# fonte_simetrica.net
KiCad netlist of a schematic drawn in EAGLE
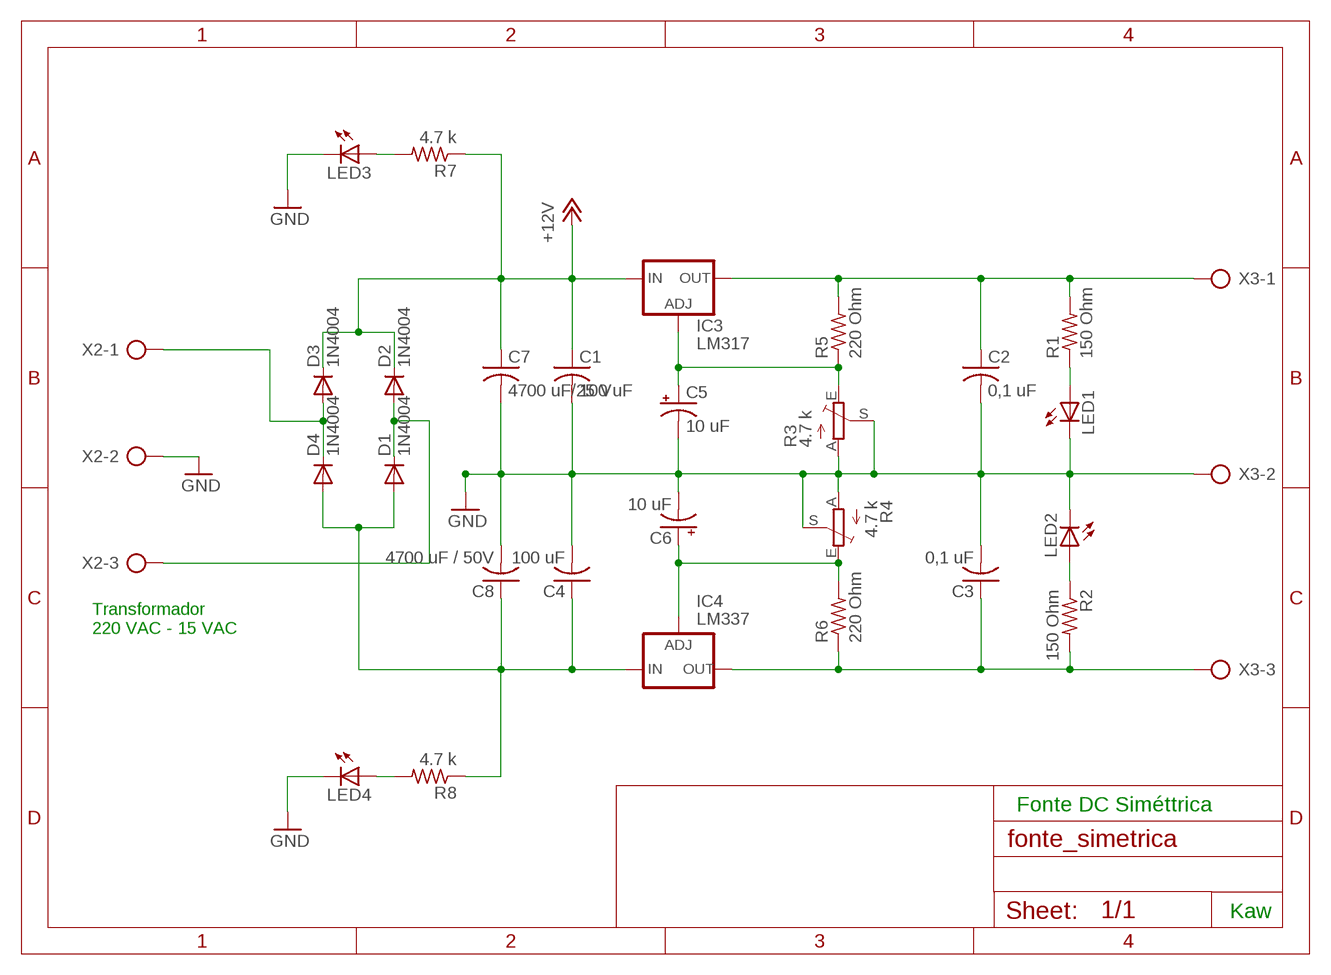
[diagram p0: schematic, sheet 1]

(export (version "E")
  (design (tool "Eeschema 10.0.6"))
  (components
    (comp (ref "C1")
      (value "100 uF")
      (footprint "eagle-import:C025-025X050")
      (libsource (lib "eagle-import") (part "C-US025-025X050"))
    )
    (comp (ref "C2")
      (value "0,1 uF")
      (footprint "eagle-import:C025-025X050")
      (libsource (lib "eagle-import") (part "C-US025-025X050"))
    )
    (comp (ref "C3")
      (value "0,1 uF")
      (footprint "eagle-import:C025-025X050")
      (libsource (lib "eagle-import") (part "C-US025-025X050"))
    )
    (comp (ref "C4")
      (value "100 uF")
      (footprint "eagle-import:C025-025X050")
      (libsource (lib "eagle-import") (part "C-US025-025X050"))
    )
    (comp (ref "C5")
      (value "10 uF")
      (footprint "eagle-import:E2,5-4R")
      (libsource (lib "eagle-import") (part "CPOL-USE2.5-5V"))
    )
    (comp (ref "C6")
      (value "10 uF")
      (footprint "eagle-import:E2,5-4R")
      (libsource (lib "eagle-import") (part "CPOL-USE2.5-5V"))
    )
    (comp (ref "C7")
      (value "4700 uF/25 V")
      (footprint "eagle-import:C025-025X050")
      (libsource (lib "eagle-import") (part "C-US025-025X050"))
    )
    (comp (ref "C8")
      (value "4700 uF / 50V")
      (footprint "eagle-import:C025-025X050")
      (libsource (lib "eagle-import") (part "C-US025-025X050"))
    )
    (comp (ref "D1")
      (value "1N4004")
      (footprint "eagle-import:DO41-10")
      (libsource (lib "eagle-import") (part "1N4004"))
    )
    (comp (ref "D2")
      (value "1N4004")
      (footprint "eagle-import:DO41-10")
      (libsource (lib "eagle-import") (part "1N4004"))
    )
    (comp (ref "D3")
      (value "1N4004")
      (footprint "eagle-import:DO41-10")
      (libsource (lib "eagle-import") (part "1N4004"))
    )
    (comp (ref "D4")
      (value "1N4004")
      (footprint "eagle-import:DO41-10")
      (libsource (lib "eagle-import") (part "1N4004"))
    )
    (comp (ref "IC3")
      (value "LM317")
      (footprint "eagle-import:317TS")
      (libsource (lib "eagle-import") (part "LM317TS"))
    )
    (comp (ref "IC4")
      (value "LM337")
      (footprint "eagle-import:337TS")
      (libsource (lib "eagle-import") (part "LM337TS"))
    )
    (comp (ref "LED1")
      (value "LED5MM")
      (footprint "eagle-import:LED5MM")
      (libsource (lib "eagle-import") (part "LED5MM"))
    )
    (comp (ref "LED2")
      (value "LED5MM")
      (footprint "eagle-import:LED5MM")
      (libsource (lib "eagle-import") (part "LED5MM"))
    )
    (comp (ref "LED3")
      (value "LED5MM")
      (footprint "eagle-import:LED5MM")
      (libsource (lib "eagle-import") (part "LED5MM"))
    )
    (comp (ref "LED4")
      (value "LED5MM")
      (footprint "eagle-import:LED5MM")
      (libsource (lib "eagle-import") (part "LED5MM"))
    )
    (comp (ref "R1")
      (value "150 Ohm")
      (footprint "eagle-import:0207_5V")
      (libsource (lib "eagle-import") (part "R-US_0207/5V"))
    )
    (comp (ref "R2")
      (value "150 Ohm")
      (footprint "eagle-import:0207_5V")
      (libsource (lib "eagle-import") (part "R-US_0207/5V"))
    )
    (comp (ref "R3")
      (value "4.7 k")
      (footprint "eagle-import:S64W")
      (libsource (lib "eagle-import") (part "TRIM_EU-S64W"))
    )
    (comp (ref "R4")
      (value "4.7 k")
      (footprint "eagle-import:S64W")
      (libsource (lib "eagle-import") (part "TRIM_EU-S64W"))
    )
    (comp (ref "R5")
      (value "220 Ohm")
      (footprint "eagle-import:0207_5V")
      (libsource (lib "eagle-import") (part "R-US_0207/5V"))
    )
    (comp (ref "R6")
      (value "220 Ohm")
      (footprint "eagle-import:0207_5V")
      (libsource (lib "eagle-import") (part "R-US_0207/5V"))
    )
    (comp (ref "R7")
      (value "4.7 k")
      (footprint "eagle-import:0207_5V")
      (libsource (lib "eagle-import") (part "R-US_0207/5V"))
    )
    (comp (ref "R8")
      (value "4.7 k")
      (footprint "eagle-import:0207_5V")
      (libsource (lib "eagle-import") (part "R-US_0207/5V"))
    )
    (comp (ref "X2")
      (value "AK300/3")
      (footprint "eagle-import:AK300_3")
      (libsource (lib "eagle-import") (part "AK300/3"))
    )
    (comp (ref "X3")
      (value "AK300/3")
      (footprint "eagle-import:AK300_3")
      (libsource (lib "eagle-import") (part "AK300/3"))
    )
  )
  (nets
    (net (code "1") (name "+12V") (class "Default")
      (node (ref "C1") (pin "1") (pinfunction "1_1") (pintype "passive"))
      (node (ref "C7") (pin "1") (pinfunction "1_1") (pintype "passive"))
      (node (ref "D2") (pin "C") (pinfunction "C_C") (pintype "passive"))
      (node (ref "D3") (pin "C") (pinfunction "C_C") (pintype "passive"))
      (node (ref "IC3") (pin "3") (pinfunction "IN_3") (pintype "input"))
      (node (ref "R7") (pin "1") (pinfunction "1_1") (pintype "passive"))
    )
    (net (code "2") (name "GND") (class "Default")
      (node (ref "C1") (pin "2") (pinfunction "2_2") (pintype "passive"))
      (node (ref "C2") (pin "2") (pinfunction "2_2") (pintype "passive"))
      (node (ref "C3") (pin "2") (pinfunction "2_2") (pintype "passive"))
      (node (ref "C4") (pin "2") (pinfunction "2_2") (pintype "passive"))
      (node (ref "C5") (pin "-") (pinfunction "-_-") (pintype "passive"))
      (node (ref "C6") (pin "-") (pinfunction "-_-") (pintype "passive"))
      (node (ref "C7") (pin "2") (pinfunction "2_2") (pintype "passive"))
      (node (ref "C8") (pin "2") (pinfunction "2_2") (pintype "passive"))
      (node (ref "LED1") (pin "K") (pinfunction "C_K") (pintype "passive"))
      (node (ref "LED2") (pin "K") (pinfunction "C_K") (pintype "passive"))
      (node (ref "LED3") (pin "K") (pinfunction "C_K") (pintype "passive"))
      (node (ref "LED4") (pin "K") (pinfunction "C_K") (pintype "passive"))
      (node (ref "R3") (pin "A") (pinfunction "A_A") (pintype "passive"))
      (node (ref "R3") (pin "S") (pinfunction "S_S") (pintype "passive"))
      (node (ref "R4") (pin "A") (pinfunction "A_A") (pintype "passive"))
      (node (ref "R4") (pin "S") (pinfunction "S_S") (pintype "passive"))
      (node (ref "X2") (pin "2") (pinfunction "KL_2") (pintype "passive"))
      (node (ref "X3") (pin "2") (pinfunction "KL_2") (pintype "passive"))
    )
    (net (code "3") (name "Net-(IC3-ADJ)") (class "Default")
      (node (ref "C5") (pin "+") (pinfunction "+_+") (pintype "passive"))
      (node (ref "IC3") (pin "1") (pinfunction "ADJ_1") (pintype "input"))
      (node (ref "R3") (pin "E") (pinfunction "E_E") (pintype "passive"))
      (node (ref "R5") (pin "1") (pinfunction "1_1") (pintype "passive"))
    )
    (net (code "4") (name "Net-(IC3-OUT)") (class "Default")
      (node (ref "C2") (pin "1") (pinfunction "1_1") (pintype "passive"))
      (node (ref "IC3") (pin "2") (pinfunction "OUT_2") (pintype "passive"))
      (node (ref "R1") (pin "2") (pinfunction "2_2") (pintype "passive"))
      (node (ref "R5") (pin "2") (pinfunction "2_2") (pintype "passive"))
      (node (ref "X3") (pin "1") (pinfunction "KL_1") (pintype "passive"))
    )
    (net (code "5") (name "Net-(IC4-ADJ)") (class "Default")
      (node (ref "C6") (pin "+") (pinfunction "+_+") (pintype "passive"))
      (node (ref "IC4") (pin "1") (pinfunction "ADJ_1") (pintype "input"))
      (node (ref "R4") (pin "E") (pinfunction "E_E") (pintype "passive"))
      (node (ref "R6") (pin "2") (pinfunction "2_2") (pintype "passive"))
    )
    (net (code "6") (name "Net-(IC4-IN)") (class "Default")
      (node (ref "C4") (pin "1") (pinfunction "1_1") (pintype "passive"))
      (node (ref "C8") (pin "1") (pinfunction "1_1") (pintype "passive"))
      (node (ref "D1") (pin "A") (pinfunction "A_A") (pintype "passive"))
      (node (ref "D4") (pin "A") (pinfunction "A_A") (pintype "passive"))
      (node (ref "IC4") (pin "2") (pinfunction "IN_2") (pintype "input"))
      (node (ref "R8") (pin "1") (pinfunction "1_1") (pintype "passive"))
    )
    (net (code "7") (name "Net-(IC4-OUT)") (class "Default")
      (node (ref "C3") (pin "1") (pinfunction "1_1") (pintype "passive"))
      (node (ref "IC4") (pin "3") (pinfunction "OUT_3") (pintype "passive"))
      (node (ref "R2") (pin "2") (pinfunction "2_2") (pintype "passive"))
      (node (ref "R6") (pin "1") (pinfunction "1_1") (pintype "passive"))
      (node (ref "X3") (pin "3") (pinfunction "KL_3") (pintype "passive"))
    )
    (net (code "8") (name "Net-(LED1-PadA)") (class "Default")
      (node (ref "LED1") (pin "A") (pinfunction "A_A") (pintype "passive"))
      (node (ref "R1") (pin "1") (pinfunction "1_1") (pintype "passive"))
    )
    (net (code "9") (name "Net-(LED2-PadA)") (class "Default")
      (node (ref "LED2") (pin "A") (pinfunction "A_A") (pintype "passive"))
      (node (ref "R2") (pin "1") (pinfunction "1_1") (pintype "passive"))
    )
    (net (code "10") (name "Net-(LED3-PadA)") (class "Default")
      (node (ref "LED3") (pin "A") (pinfunction "A_A") (pintype "passive"))
      (node (ref "R7") (pin "2") (pinfunction "2_2") (pintype "passive"))
    )
    (net (code "11") (name "Net-(LED4-PadA)") (class "Default")
      (node (ref "LED4") (pin "A") (pinfunction "A_A") (pintype "passive"))
      (node (ref "R8") (pin "2") (pinfunction "2_2") (pintype "passive"))
    )
    (net (code "12") (name "Net-(X2A-KL)") (class "Default")
      (node (ref "D3") (pin "A") (pinfunction "A_A") (pintype "passive"))
      (node (ref "D4") (pin "C") (pinfunction "C_C") (pintype "passive"))
      (node (ref "X2") (pin "1") (pinfunction "KL_1") (pintype "passive"))
    )
    (net (code "13") (name "Net-(X2C-KL)") (class "Default")
      (node (ref "D1") (pin "C") (pinfunction "C_C") (pintype "passive"))
      (node (ref "D2") (pin "A") (pinfunction "A_A") (pintype "passive"))
      (node (ref "X2") (pin "3") (pinfunction "KL_3") (pintype "passive"))
    )
  )
)
